# Schematic.net
KiCad netlist of a schematic drawn in EAGLE
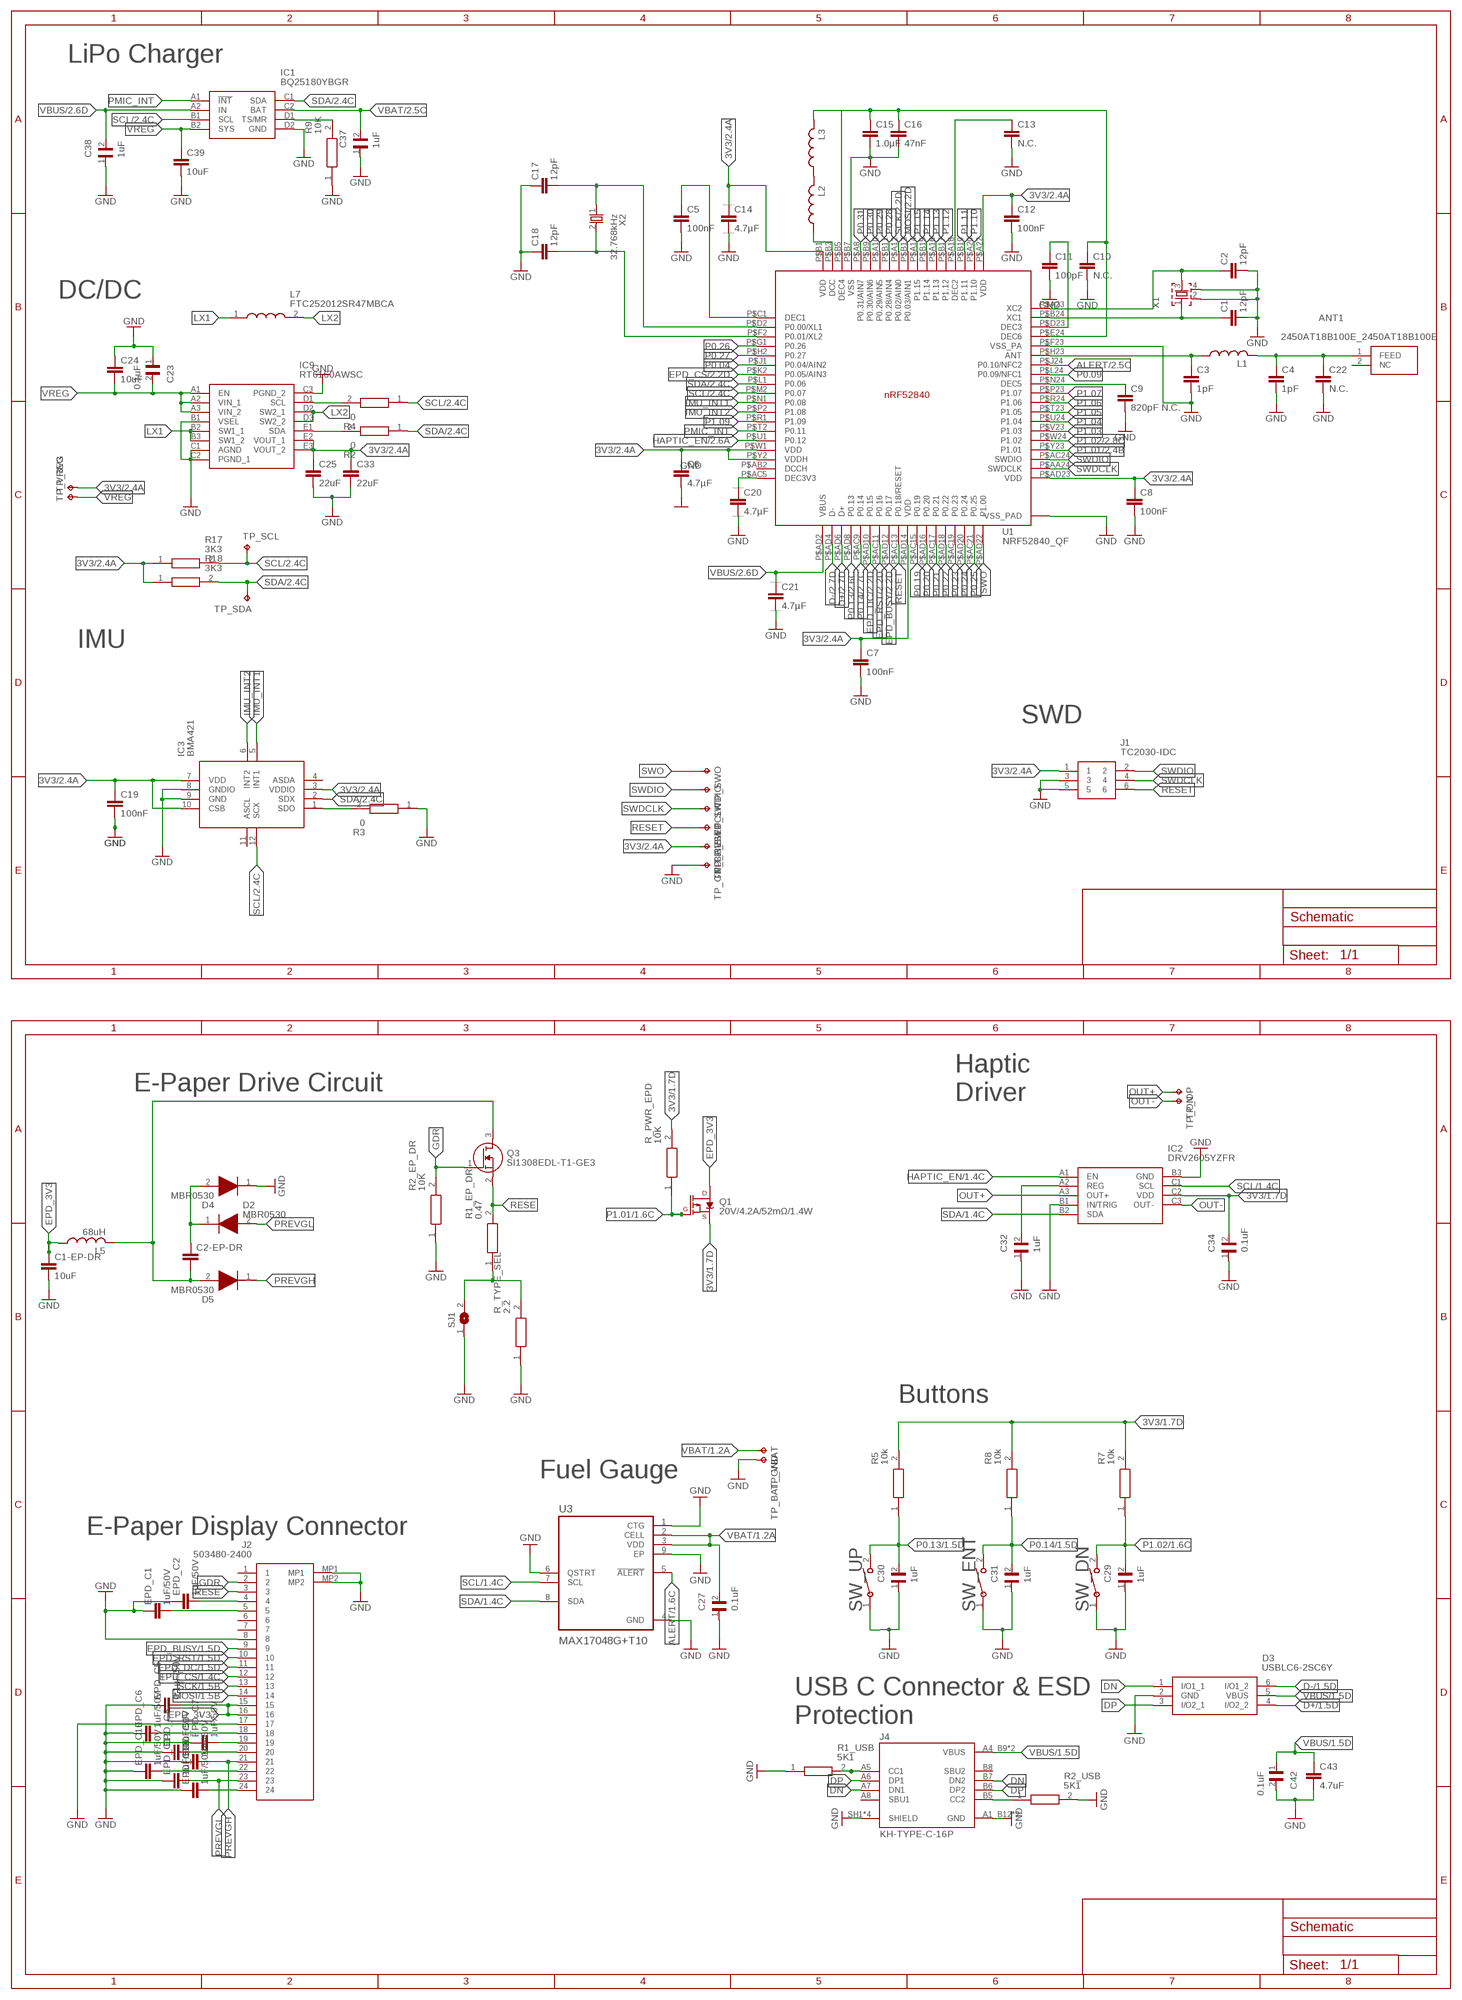
[diagram p0: schematic, sheet 1]

(export (version "E")
  (design (tool "Eeschema 10.0.6"))
  (components
    (comp (ref "ANT1")
      (value "2450AT18B100E_2450AT18B100E")
      (footprint "eagle-import:2450AT18B100E_ANTC3216X140N")
      (fields
        (field (name "ARROW_PART_NUMBER") "2450AT18B100E")
        (field (name "MOUSER_PART_NUMBER") "609-2450AT18B100E")
      )
      (libsource (lib "eagle-import") (part "2450AT18B100E_2450AT18B100E"))
    )
    (comp (ref "C1")
      (value "12pF")
      (footprint "eagle-import:NORDIC_NRF_3_RESC0201_L")
      (libsource (lib "eagle-import") (part "NORDIC_NRF_3_CAPACITOR_0201_L"))
    )
    (comp (ref "C1-EP-DR")
      (value "10uF")
      (footprint "eagle-import:NORDIC_NRF_3_RESC0201_L")
      (libsource (lib "eagle-import") (part "NORDIC_NRF_3_CAPACITOR_0201_L"))
    )
    (comp (ref "C2")
      (value "12pF")
      (footprint "eagle-import:NORDIC_NRF_3_RESC0201_L")
      (libsource (lib "eagle-import") (part "NORDIC_NRF_3_CAPACITOR_0201_L"))
    )
    (comp (ref "C2-EP-DR")
      (value "NORDIC_NRF_3_CAPACITOR_0201_L")
      (footprint "eagle-import:NORDIC_NRF_3_RESC0201_L")
      (libsource (lib "eagle-import") (part "NORDIC_NRF_3_CAPACITOR_0201_L"))
    )
    (comp (ref "C3")
      (value "1pF")
      (footprint "eagle-import:NORDIC_NRF_3_RESC0201_L")
      (libsource (lib "eagle-import") (part "NORDIC_NRF_3_CAPACITOR_0201_L"))
    )
    (comp (ref "C4")
      (value "1pF")
      (footprint "eagle-import:NORDIC_NRF_3_RESC0201_L")
      (libsource (lib "eagle-import") (part "NORDIC_NRF_3_CAPACITOR_0201_L"))
    )
    (comp (ref "C5")
      (value "100nF")
      (footprint "eagle-import:NORDIC_NRF_3_RESC0201_L")
      (libsource (lib "eagle-import") (part "NORDIC_NRF_3_CAPACITOR_0201_L"))
    )
    (comp (ref "C6")
      (value "4.7µF")
      (footprint "eagle-import:NORDIC_NRF_3_RESC0201_L")
      (libsource (lib "eagle-import") (part "NORDIC_NRF_3_CAPACITOR_0201_L"))
    )
    (comp (ref "C7")
      (value "100nF")
      (footprint "eagle-import:NORDIC_NRF_3_RESC0201_L")
      (libsource (lib "eagle-import") (part "NORDIC_NRF_3_CAPACITOR_0201_L"))
    )
    (comp (ref "C8")
      (value "100nF")
      (footprint "eagle-import:NORDIC_NRF_3_RESC0201_L")
      (libsource (lib "eagle-import") (part "NORDIC_NRF_3_CAPACITOR_0201_L"))
    )
    (comp (ref "C9")
      (value "820pF N.C.")
      (footprint "eagle-import:NORDIC_NRF_3_RESC0201_L")
      (libsource (lib "eagle-import") (part "NORDIC_NRF_3_CAPACITOR_0201_L"))
    )
    (comp (ref "C10")
      (value "N.C.")
      (footprint "eagle-import:NORDIC_NRF_3_RESC0201_L")
      (libsource (lib "eagle-import") (part "NORDIC_NRF_3_CAPACITOR_0201_L"))
    )
    (comp (ref "C11")
      (value "100pF")
      (footprint "eagle-import:NORDIC_NRF_3_RESC0201_L")
      (libsource (lib "eagle-import") (part "NORDIC_NRF_3_CAPACITOR_0201_L"))
    )
    (comp (ref "C12")
      (value "100nF")
      (footprint "eagle-import:NORDIC_NRF_3_RESC0201_L")
      (libsource (lib "eagle-import") (part "NORDIC_NRF_3_CAPACITOR_0201_L"))
    )
    (comp (ref "C13")
      (value "N.C.")
      (footprint "eagle-import:NORDIC_NRF_3_RESC0201_L")
      (libsource (lib "eagle-import") (part "NORDIC_NRF_3_CAPACITOR_0201_L"))
    )
    (comp (ref "C14")
      (value "4.7µF")
      (footprint "eagle-import:ESP32_C6_LIBRARY_1_ESP32_WROVER_EAGLE-LTSPICE_C0402")
      (libsource (lib "eagle-import") (part "ESP32_C6_LIBRARY_1_ESP32_WROVER_EAGLE-LTSPICE_CC0402"))
    )
    (comp (ref "C15")
      (value "1.0µF")
      (footprint "eagle-import:NORDIC_NRF_3_RESC0201_L")
      (libsource (lib "eagle-import") (part "NORDIC_NRF_3_CAPACITOR_0201_L"))
    )
    (comp (ref "C16")
      (value "47nF")
      (footprint "eagle-import:NORDIC_NRF_3_RESC0201_L")
      (libsource (lib "eagle-import") (part "NORDIC_NRF_3_CAPACITOR_0201_L"))
    )
    (comp (ref "C17")
      (value "12pF")
      (footprint "eagle-import:NORDIC_NRF_3_RESC0201_L")
      (libsource (lib "eagle-import") (part "NORDIC_NRF_3_CAPACITOR_0201_L"))
    )
    (comp (ref "C18")
      (value "12pF")
      (footprint "eagle-import:NORDIC_NRF_3_RESC0201_L")
      (libsource (lib "eagle-import") (part "NORDIC_NRF_3_CAPACITOR_0201_L"))
    )
    (comp (ref "C19")
      (value "100nF")
      (footprint "eagle-import:NORDIC_NRF_3_RESC0201_L")
      (libsource (lib "eagle-import") (part "NORDIC_NRF_3_CAPACITOR_0201_L"))
    )
    (comp (ref "C20")
      (value "4.7µF")
      (footprint "eagle-import:ESP32_C6_LIBRARY_1_ESP32_WROVER_EAGLE-LTSPICE_C0402")
      (libsource (lib "eagle-import") (part "ESP32_C6_LIBRARY_1_ESP32_WROVER_EAGLE-LTSPICE_CC0402"))
    )
    (comp (ref "C21")
      (value "4.7µF")
      (footprint "eagle-import:ESP32_C6_LIBRARY_1_ESP32_WROVER_EAGLE-LTSPICE_C0402")
      (libsource (lib "eagle-import") (part "ESP32_C6_LIBRARY_1_ESP32_WROVER_EAGLE-LTSPICE_CC0402"))
    )
    (comp (ref "C22")
      (value "N.C.")
      (footprint "eagle-import:NORDIC_NRF_3_RESC0201_L")
      (libsource (lib "eagle-import") (part "NORDIC_NRF_3_CAPACITOR_0201_L"))
    )
    (comp (ref "C23")
      (value "0.1uF")
      (footprint "eagle-import:GRM011R60J152KE01L_2_CAPC0201X13N")
      (fields (field (name "MF") "Murata") (field (name "MP") "GRM011R60J152KE01L"))
      (libsource (lib "eagle-import") (part "GRM011R60J152KE01L_2_GRM011R60J152KE01L"))
    )
    (comp (ref "C24")
      (value "10uF")
      (footprint "eagle-import:NORDIC_NRF_3_RESC0201_L")
      (libsource (lib "eagle-import") (part "InkTime_v5_vf.zRXQ1UkXTZ2guy9XbI6Eng_NORDIC_NRF_3_CAPACITOR_0201_L"))
    )
    (comp (ref "C25")
      (value "22uF")
      (footprint "eagle-import:NORDIC_NRF_3_RESC0201_L")
      (libsource (lib "eagle-import") (part "InkTime_v5_vf.zRXQ1UkXTZ2guy9XbI6Eng_NORDIC_NRF_3_CAPACITOR_0201_L"))
    )
    (comp (ref "C27")
      (value "0.1uF")
      (footprint "eagle-import:GRM011R60J152KE01L_1_0201")
      (libsource (lib "eagle-import") (part "GRM011R60J152KE01L_1_GRM011R60J152KE01L"))
    )
    (comp (ref "C29")
      (value "1uF")
      (footprint "eagle-import:GRM011R60J152KE01L_1_0201")
      (libsource (lib "eagle-import") (part "GRM011R60J152KE01L_1_GRM011R60J152KE01L"))
    )
    (comp (ref "C30")
      (value "1uF")
      (footprint "eagle-import:GRM011R60J152KE01L_1_0201")
      (libsource (lib "eagle-import") (part "GRM011R60J152KE01L_1_GRM011R60J152KE01L"))
    )
    (comp (ref "C31")
      (value "1uF")
      (footprint "eagle-import:GRM011R60J152KE01L_1_0201")
      (libsource (lib "eagle-import") (part "GRM011R60J152KE01L_1_GRM011R60J152KE01L"))
    )
    (comp (ref "C32")
      (value "1uF")
      (footprint "eagle-import:GRM011R60J152KE01L_2_CAPC0201X13N")
      (fields (field (name "MF") "Murata") (field (name "MP") "GRM011R60J152KE01L"))
      (libsource (lib "eagle-import") (part "GRM011R60J152KE01L_2_GRM011R60J152KE01L"))
    )
    (comp (ref "C33")
      (value "22uF")
      (footprint "eagle-import:NORDIC_NRF_3_RESC0201_L")
      (libsource (lib "eagle-import") (part "InkTime_v5_vf.zRXQ1UkXTZ2guy9XbI6Eng_NORDIC_NRF_3_CAPACITOR_0201_L"))
    )
    (comp (ref "C34")
      (value "0.1uF")
      (footprint "eagle-import:GRM011R60J152KE01L_2_CAPC0201X13N")
      (fields (field (name "MF") "Murata") (field (name "MP") "GRM011R60J152KE01L"))
      (libsource (lib "eagle-import") (part "GRM011R60J152KE01L_2_GRM011R60J152KE01L"))
    )
    (comp (ref "C37")
      (value "1uF")
      (footprint "eagle-import:GRM011R60J152KE01L_2_CAPC0201X13N")
      (fields (field (name "MF") "Murata") (field (name "MP") "GRM011R60J152KE01L"))
      (libsource (lib "eagle-import") (part "GRM011R60J152KE01L_2_GRM011R60J152KE01L"))
    )
    (comp (ref "C38")
      (value "1uF")
      (footprint "eagle-import:GRM011R60J152KE01L_2_CAPC0201X13N")
      (fields (field (name "MF") "Murata") (field (name "MP") "GRM011R60J152KE01L"))
      (libsource (lib "eagle-import") (part "GRM011R60J152KE01L_2_GRM011R60J152KE01L"))
    )
    (comp (ref "C39")
      (value "10uF")
      (footprint "eagle-import:NORDIC_NRF_3_RESC0201_L")
      (libsource (lib "eagle-import") (part "InkTime_v5_vf.zRXQ1UkXTZ2guy9XbI6Eng_NORDIC_NRF_3_CAPACITOR_0201_L"))
    )
    (comp (ref "C42")
      (value "0.1uF")
      (footprint "eagle-import:GRM011R60J152KE01L_1_0201")
      (libsource (lib "eagle-import") (part "GRM011R60J152KE01L_1_GRM011R60J152KE01L"))
    )
    (comp (ref "C43")
      (value "4.7uF")
      (footprint "eagle-import:NORDIC_NRF_3_RESC0201_L")
      (libsource (lib "eagle-import") (part "InkTime_v5_vf.zRXQ1UkXTZ2guy9XbI6Eng_NORDIC_NRF_3_CAPACITOR_0201_L"))
    )
    (comp (ref "D2")
      (value "MBR0530")
      (footprint "eagle-import:ESP32_C6_LIBRARY_5_SOD3716X135N")
      (fields (field (name "MF") "ON Semiconductor"))
      (libsource (lib "eagle-import") (part "ESP32_C6_LIBRARY_5_MBR0530"))
    )
    (comp (ref "D3")
      (value "USBLC6-2SC6Y")
      (footprint "eagle-import:ESP32_C6_LIBRARY_3_SOT95P280X145-6N")
      (fields (field (name "MF") "STMicroelectronics"))
      (libsource (lib "eagle-import") (part "ESP32_C6_LIBRARY_3_USBLC6-2SC6Y"))
    )
    (comp (ref "D4")
      (value "MBR0530")
      (footprint "eagle-import:ESP32_C6_LIBRARY_5_SOD3716X135N")
      (fields (field (name "MF") "ON Semiconductor"))
      (libsource (lib "eagle-import") (part "ESP32_C6_LIBRARY_5_MBR0530"))
    )
    (comp (ref "D5")
      (value "MBR0530")
      (footprint "eagle-import:ESP32_C6_LIBRARY_5_SOD3716X135N")
      (fields (field (name "MF") "ON Semiconductor"))
      (libsource (lib "eagle-import") (part "ESP32_C6_LIBRARY_5_MBR0530"))
    )
    (comp (ref "EPD_C1")
      (value "1uF/50V")
      (footprint "eagle-import:PERFECT_0402_0402")
      (libsource (lib "eagle-import") (part "PERFECT_0402_CAP_0402"))
    )
    (comp (ref "EPD_C2")
      (value "1uF/50V")
      (footprint "eagle-import:PERFECT_0402_0402")
      (libsource (lib "eagle-import") (part "PERFECT_0402_CAP_0402"))
    )
    (comp (ref "EPD_C5")
      (value "0.1uF/50V")
      (footprint "eagle-import:PERFECT_0402_0402")
      (libsource (lib "eagle-import") (part "PERFECT_0402_CAP_0402"))
    )
    (comp (ref "EPD_C6")
      (value "1uF/50V")
      (footprint "eagle-import:PERFECT_0402_0402")
      (libsource (lib "eagle-import") (part "PERFECT_0402_CAP_0402"))
    )
    (comp (ref "EPD_C7")
      (value "1uF/50V")
      (footprint "eagle-import:PERFECT_0402_0402")
      (libsource (lib "eagle-import") (part "PERFECT_0402_CAP_0402"))
    )
    (comp (ref "EPD_C8")
      (value "1uF/50V")
      (footprint "eagle-import:PERFECT_0402_0402")
      (libsource (lib "eagle-import") (part "PERFECT_0402_CAP_0402"))
    )
    (comp (ref "EPD_C9")
      (value "1uF/50V")
      (footprint "eagle-import:PERFECT_0402_0402")
      (libsource (lib "eagle-import") (part "PERFECT_0402_CAP_0402"))
    )
    (comp (ref "EPD_C10")
      (value "1uF/50V")
      (footprint "eagle-import:PERFECT_0402_0402")
      (libsource (lib "eagle-import") (part "PERFECT_0402_CAP_0402"))
    )
    (comp (ref "EPD_C11")
      (value "1uF/50V")
      (footprint "eagle-import:PERFECT_0402_0402")
      (libsource (lib "eagle-import") (part "PERFECT_0402_CAP_0402"))
    )
    (comp (ref "EPD_C12")
      (value "1uF/50V")
      (footprint "eagle-import:PERFECT_0402_0402")
      (libsource (lib "eagle-import") (part "PERFECT_0402_CAP_0402"))
    )
    (comp (ref "IC1")
      (value "BQ25180YBGR")
      (footprint "eagle-import:BQ25180YBGR_BGA8C40P2X4_100X155X50")
      (fields (field (name "MOUSER_PART_NUMBER") "595-BQ25180YBGR"))
      (libsource (lib "eagle-import") (part "BQ25180YBGR_BQ25180YBGR"))
    )
    (comp (ref "IC2")
      (value "DRV2605YZFR")
      (footprint "eagle-import:DRV2605YZFR_BGA9C50P3X3_144X144X62")
      (libsource (lib "eagle-import") (part "DRV2605YZFR_DRV2605YZFR"))
    )
    (comp (ref "IC3")
      (value "BMA421")
      (footprint "eagle-import:BMA423_BMA423")
      (fields (field (name "ARROW_PART_NUMBER") "BMA423") (field (name "MOUSER_PART_NUMBER") "262-BMA423"))
      (libsource (lib "eagle-import") (part "BMA423_BMA423"))
    )
    (comp (ref "IC9")
      (value "RT6160AWSC")
      (footprint "eagle-import:RT6160AWSC_BGA15C40P3X5_140X230X60")
      (fields (field (name "MOUSER_PART_NUMBER") "835-RT6160AWSC"))
      (libsource (lib "eagle-import") (part "RT6160AWSC_RT6160AWSC"))
    )
    (comp (ref "J1")
      (value "TC2030-IDC")
      (footprint "eagle-import:TC2030-IDC_TC2030IDC")
      (libsource (lib "eagle-import") (part "TC2030-IDC_TC2030-IDC"))
    )
    (comp (ref "J2")
      (value "503480-2400")
      (footprint "eagle-import:503480-2400_5034802400")
      (fields (field (name "MOUSER_PART_NUMBER") "538-503480-2400"))
      (libsource (lib "eagle-import") (part "503480-2400_503480-2400"))
    )
    (comp (ref "J4")
      (value "KH-TYPE-C-16P")
      (footprint "eagle-import:KH-TYPE-C-16P_KINGHELM_KH-TYPE-C-16P")
      (fields (field (name "MF") "kinghelm"))
      (libsource (lib "eagle-import") (part "KH-TYPE-C-16P_KH-TYPE-C-16P"))
    )
    (comp (ref "L1")
      (value "NORDIC_NRF_2_INDUCTOR_0402_L")
      (footprint "eagle-import:NORDIC_NRF_2_RESC0402_L")
      (libsource (lib "eagle-import") (part "NORDIC_NRF_2_INDUCTOR_0402_L"))
    )
    (comp (ref "L2")
      (value "NORDIC_NRF_2_INDUCTOR_0402_L")
      (footprint "eagle-import:NORDIC_NRF_2_RESC0402_L")
      (libsource (lib "eagle-import") (part "NORDIC_NRF_2_INDUCTOR_0402_L"))
    )
    (comp (ref "L3")
      (value "NORDIC_NRF_2_INDUCTOR_0402_L")
      (footprint "eagle-import:NORDIC_NRF_2_RESC0402_L")
      (libsource (lib "eagle-import") (part "NORDIC_NRF_2_INDUCTOR_0402_L"))
    )
    (comp (ref "L5")
      (value "68uH")
      (footprint "eagle-import:NORDIC_NRF_2_RESC0402_L")
      (libsource (lib "eagle-import") (part "NORDIC_NRF_2_INDUCTOR_0402_L"))
    )
    (comp (ref "L7")
      (value "FTC252012SR47MBCA")
      (footprint "eagle-import:MLP2016SR47MT0S1_INDC2016X100N")
      (libsource (lib "eagle-import") (part "MLP2016SR47MT0S1_FTC252012SR47MBCA"))
    )
    (comp (ref "Q1")
      (value "20V/4.2A/52mΩ/1.4W")
      (footprint "eagle-import:ESP32_C6_LIBRARY_4_ESP32_C6_LIBRARY_4_ESP32_C6_LIBRARY_4_ESP32_C6_LIBRARY_4_ESP32_WROVER_SPARKFUN-DISCRETESEMI_SOT23-3")
      (libsource (lib "eagle-import") (part "ESP32_C6_LIBRARY_4_ESP32_WROVER_SPARKFUN-DISCRETESEMI_MOSFET_PCH-DMG2305UX-7"))
    )
    (comp (ref "Q3")
      (value "SI1308EDL-T1-GE3")
      (footprint "eagle-import:ESP32_C6_LIBRARY_6_SOT65P210X110-3N")
      (fields (field (name "MF") "Vishay Siliconix"))
      (libsource (lib "eagle-import") (part "ESP32_C6_LIBRARY_6_SI1308EDL-T1-GE3"))
    )
    (comp (ref "R1_EP_DR")
      (value "0.47")
      (footprint "eagle-import:ERA-1AEB3401C_0201")
      (libsource (lib "eagle-import") (part "ERA-1AEB3401C_CPF0201D7K68C1"))
    )
    (comp (ref "R1_USB")
      (value "5K1")
      (footprint "eagle-import:CPF0201D7K68C1_0201")
      (libsource (lib "eagle-import") (part "InkTime_v5_vf.zRXQ1UkXTZ2guy9XbI6Eng_CPF0201D7K68C1_CPF0201D7K68C1"))
    )
    (comp (ref "R2")
      (value "0")
      (footprint "eagle-import:ERA-1AEB3401C_0201")
      (libsource (lib "eagle-import") (part "ERA-1AEB3401C_CPF0201D7K68C1"))
    )
    (comp (ref "R2_EP_DR")
      (value "10K")
      (footprint "eagle-import:ERA-1AEB3401C_0201")
      (libsource (lib "eagle-import") (part "ERA-1AEB3401C_CPF0201D7K68C1"))
    )
    (comp (ref "R2_USB")
      (value "5K1")
      (footprint "eagle-import:CPF0201D7K68C1_0201")
      (libsource (lib "eagle-import") (part "InkTime_v5_vf.zRXQ1UkXTZ2guy9XbI6Eng_CPF0201D7K68C1_CPF0201D7K68C1"))
    )
    (comp (ref "R3")
      (value "0")
      (footprint "eagle-import:CPF0201D7K68C1_0201")
      (libsource (lib "eagle-import") (part "CPF0201D7K68C1_CPF0201D7K68C1"))
    )
    (comp (ref "R4")
      (value "0")
      (footprint "eagle-import:ERA-1AEB3401C_0201")
      (libsource (lib "eagle-import") (part "ERA-1AEB3401C_CPF0201D7K68C1"))
    )
    (comp (ref "R5")
      (value "10k")
      (footprint "eagle-import:CPF0201D7K68C1_0201")
      (libsource (lib "eagle-import") (part "InkTime_v5_vf.zRXQ1UkXTZ2guy9XbI6Eng_CPF0201D7K68C1_CPF0201D7K68C1"))
    )
    (comp (ref "R7")
      (value "10k")
      (footprint "eagle-import:CPF0201D7K68C1_0201")
      (libsource (lib "eagle-import") (part "InkTime_v5_vf.zRXQ1UkXTZ2guy9XbI6Eng_CPF0201D7K68C1_CPF0201D7K68C1"))
    )
    (comp (ref "R8")
      (value "10k")
      (footprint "eagle-import:CPF0201D7K68C1_0201")
      (libsource (lib "eagle-import") (part "InkTime_v5_vf.zRXQ1UkXTZ2guy9XbI6Eng_CPF0201D7K68C1_CPF0201D7K68C1"))
    )
    (comp (ref "R9")
      (value "10K")
      (footprint "eagle-import:ERA-1AEB3401C_0201")
      (libsource (lib "eagle-import") (part "ERA-1AEB3401C_CPF0201D7K68C1"))
    )
    (comp (ref "R17")
      (value "3K3")
      (footprint "eagle-import:ERA-1AEB3401C_0201")
      (libsource (lib "eagle-import") (part "ERA-1AEB3401C_CPF0201D7K68C1"))
    )
    (comp (ref "R18")
      (value "3K3")
      (footprint "eagle-import:ERA-1AEB3401C_0201")
      (libsource (lib "eagle-import") (part "ERA-1AEB3401C_CPF0201D7K68C1"))
    )
    (comp (ref "R_PWR_EPD")
      (value "10K")
      (footprint "eagle-import:ERA-1AEB3401C_0201")
      (libsource (lib "eagle-import") (part "ERA-1AEB3401C_CPF0201D7K68C1"))
    )
    (comp (ref "R_TYPE_SEL")
      (value "2.2")
      (footprint "eagle-import:ERA-1AEB3401C_0201")
      (libsource (lib "eagle-import") (part "ERA-1AEB3401C_CPF0201D7K68C1"))
    )
    (comp (ref "SJ1")
      (value "ESP32_C6_LIBRARY_7_JUMPER_SJ")
      (footprint "eagle-import:ESP32_C6_LIBRARY_7_JUMPER_SJ")
      (libsource (lib "eagle-import") (part "ESP32_C6_LIBRARY_7_JUMPER_SJ"))
    )
    (comp (ref "SW_DN")
      (value "2025-10-22_07-23-44_LIBRARY_EVP-AKE31ASW_EVP-AKE31A_PAN")
      (footprint "eagle-import:2025-10-22_07-23-44_LIBRARY_SW_EVP-AKE31A_PAN")
      (fields
        (field (name "MANUFACTURER_PART_NUMBER") "EVP-AKE31A")
        (field (name "COPYRIGHT") "Copyright (C) 2025 Ultra Librarian. All rights reserved.")
      )
      (libsource (lib "eagle-import") (part "2025-10-22_07-23-44_LIBRARY_EVP-AKE31ASW_EVP-AKE31A_PAN"))
    )
    (comp (ref "SW_ENT")
      (value "2025-10-22_07-23-44_LIBRARY_EVP-AKE31ASW_EVP-AKE31A_PAN")
      (footprint "eagle-import:2025-10-22_07-23-44_LIBRARY_SW_EVP-AKE31A_PAN")
      (fields
        (field (name "MANUFACTURER_PART_NUMBER") "EVP-AKE31A")
        (field (name "COPYRIGHT") "Copyright (C) 2025 Ultra Librarian. All rights reserved.")
      )
      (libsource (lib "eagle-import") (part "2025-10-22_07-23-44_LIBRARY_EVP-AKE31ASW_EVP-AKE31A_PAN"))
    )
    (comp (ref "SW_UP")
      (value "2025-10-22_07-23-44_LIBRARY_EVP-AKE31ASW_EVP-AKE31A_PAN")
      (footprint "eagle-import:2025-10-22_07-23-44_LIBRARY_SW_EVP-AKE31A_PAN")
      (fields
        (field (name "MANUFACTURER_PART_NUMBER") "EVP-AKE31A")
        (field (name "COPYRIGHT") "Copyright (C) 2025 Ultra Librarian. All rights reserved.")
      )
      (libsource (lib "eagle-import") (part "2025-10-22_07-23-44_LIBRARY_EVP-AKE31ASW_EVP-AKE31A_PAN"))
    )
    (comp (ref "TP_3.3V")
      (value "HECTOR_WATCH_1_TPTP20R")
      (footprint "eagle-import:HECTOR_WATCH_1_TP20R")
      (libsource (lib "eagle-import") (part "HECTOR_WATCH_1_TPTP20R"))
    )
    (comp (ref "TP_3V3")
      (value "HECTOR_WATCH_1_TPTP20R")
      (footprint "eagle-import:HECTOR_WATCH_1_TP20R")
      (libsource (lib "eagle-import") (part "InkTime_v5_vf.zRXQ1UkXTZ2guy9XbI6Eng_HECTOR_WATCH_1_TPTP20R"))
    )
    (comp (ref "TP_BAT_GND")
      (value "HECTOR_WATCH_1_TPTP20R")
      (footprint "eagle-import:HECTOR_WATCH_1_TP20R")
      (libsource (lib "eagle-import") (part "InkTime_v5_vf.zRXQ1UkXTZ2guy9XbI6Eng_HECTOR_WATCH_1_TPTP20R"))
    )
    (comp (ref "TP_GND")
      (value "HECTOR_WATCH_1_TPTP20R")
      (footprint "eagle-import:HECTOR_WATCH_1_TP20R")
      (libsource (lib "eagle-import") (part "HECTOR_WATCH_1_TPTP20R"))
    )
    (comp (ref "TP_ON")
      (value "HECTOR_WATCH_1_TPTP20R")
      (footprint "eagle-import:HECTOR_WATCH_1_TP20R")
      (libsource (lib "eagle-import") (part "HECTOR_WATCH_1_TPTP20R"))
    )
    (comp (ref "TP_OP")
      (value "HECTOR_WATCH_1_TPTP20R")
      (footprint "eagle-import:HECTOR_WATCH_1_TP20R")
      (libsource (lib "eagle-import") (part "HECTOR_WATCH_1_TPTP20R"))
    )
    (comp (ref "TP_RESET")
      (value "HECTOR_WATCH_1_TPTP20R")
      (footprint "eagle-import:HECTOR_WATCH_1_TP20R")
      (libsource (lib "eagle-import") (part "HECTOR_WATCH_1_TPTP20R"))
    )
    (comp (ref "TP_SCL")
      (value "HECTOR_WATCH_1_TPTP20R")
      (footprint "eagle-import:HECTOR_WATCH_1_TP20R")
      (libsource (lib "eagle-import") (part "HECTOR_WATCH_1_TPTP20R"))
    )
    (comp (ref "TP_SDA")
      (value "HECTOR_WATCH_1_TPTP20R")
      (footprint "eagle-import:HECTOR_WATCH_1_TP20R")
      (libsource (lib "eagle-import") (part "HECTOR_WATCH_1_TPTP20R"))
    )
    (comp (ref "TP_SWDCLK")
      (value "HECTOR_WATCH_1_TPTP20R")
      (footprint "eagle-import:HECTOR_WATCH_1_TP20R")
      (libsource (lib "eagle-import") (part "HECTOR_WATCH_1_TPTP20R"))
    )
    (comp (ref "TP_SWDIO")
      (value "HECTOR_WATCH_1_TPTP20R")
      (footprint "eagle-import:HECTOR_WATCH_1_TP20R")
      (libsource (lib "eagle-import") (part "HECTOR_WATCH_1_TPTP20R"))
    )
    (comp (ref "TP_SWO")
      (value "HECTOR_WATCH_1_TPTP20R")
      (footprint "eagle-import:HECTOR_WATCH_1_TP20R")
      (libsource (lib "eagle-import") (part "HECTOR_WATCH_1_TPTP20R"))
    )
    (comp (ref "TP_VBAT")
      (value "HECTOR_WATCH_1_TPTP20R")
      (footprint "eagle-import:HECTOR_WATCH_1_TP20R")
      (libsource (lib "eagle-import") (part "InkTime_v5_vf.zRXQ1UkXTZ2guy9XbI6Eng_HECTOR_WATCH_1_TPTP20R"))
    )
    (comp (ref "TP_VREG")
      (value "HECTOR_WATCH_1_TPTP20R")
      (footprint "eagle-import:HECTOR_WATCH_1_TP20R")
      (libsource (lib "eagle-import") (part "InkTime_v5_vf.zRXQ1UkXTZ2guy9XbI6Eng_HECTOR_WATCH_1_TPTP20R"))
    )
    (comp (ref "U1")
      (value "NRF52840_QF")
      (footprint "eagle-import:NORDIC_NRF_4_AQFN50P700X700X85_HS-74N")
      (libsource (lib "eagle-import") (part "NORDIC_NRF_4_NRF52840_QF"))
    )
    (comp (ref "U3")
      (value "MAX17048G+T10")
      (footprint "eagle-import:ESP32_C6_LIBRARY_SON50P200X200X80-9N")
      (fields (field (name "MF") "Analog Devices"))
      (libsource (lib "eagle-import") (part "ESP32_C6_LIBRARY_MAX17048G+T10"))
    )
    (comp (ref "X1")
      (value "NORDIC_NRF_XTAL_32MHZ")
      (footprint "eagle-import:NORDIC_NRF_BT-XTAL_2016_N")
      (libsource (lib "eagle-import") (part "NORDIC_NRF_XTAL_32MHZ"))
    )
    (comp (ref "X2")
      (value "32.768kHz")
      (footprint "eagle-import:NORDIC_NRF_1_XTAL_3215_N")
      (libsource (lib "eagle-import") (part "NORDIC_NRF_1_XTAL_32KHZ"))
    )
  )
  (nets
    (net (code "1") (name "3V3{slash}1.7D") (class "Default")
      (node (ref "C34") (pin "2") (pinfunction "2_2") (pintype "passive"))
      (node (ref "IC2") (pin "C2") (pinfunction "VDD_C2") (pintype "bidirectional"))
      (node (ref "Q1") (pin "2") (pinfunction "S_2") (pintype "bidirectional"))
      (node (ref "R5") (pin "2") (pinfunction "2_2") (pintype "bidirectional"))
      (node (ref "R7") (pin "2") (pinfunction "2_2") (pintype "bidirectional"))
      (node (ref "R8") (pin "2") (pinfunction "2_2") (pintype "bidirectional"))
      (node (ref "R_PWR_EPD") (pin "2") (pinfunction "2_2") (pintype "bidirectional"))
    )
    (net (code "2") (name "3V3{slash}2.4A") (class "Default")
      (node (ref "C12") (pin "1") (pinfunction "1_1") (pintype "passive"))
      (node (ref "C14") (pin "1") (pinfunction "1_1") (pintype "passive"))
      (node (ref "C19") (pin "1") (pinfunction "1_1") (pintype "passive"))
      (node (ref "C25") (pin "1") (pinfunction "1_1") (pintype "passive"))
      (node (ref "C33") (pin "1") (pinfunction "1_1") (pintype "passive"))
      (node (ref "C6") (pin "1") (pinfunction "1_1") (pintype "passive"))
      (node (ref "C7") (pin "1") (pinfunction "1_1") (pintype "passive"))
      (node (ref "C8") (pin "1") (pinfunction "1_1") (pintype "passive"))
      (node (ref "IC3") (pin "10") (pinfunction "CSB_10") (pintype "bidirectional"))
      (node (ref "IC3") (pin "3") (pinfunction "VDDIO_3") (pintype "bidirectional"))
      (node (ref "IC3") (pin "7") (pinfunction "VDD_7") (pintype "bidirectional"))
      (node (ref "IC9") (pin "E2") (pinfunction "VOUT_1_E2") (pintype "bidirectional"))
      (node (ref "IC9") (pin "E3") (pinfunction "VOUT_2_E3") (pintype "bidirectional"))
      (node (ref "J1") (pin "1") (pinfunction "1_1") (pintype "bidirectional"))
      (node (ref "R17") (pin "1") (pinfunction "1_1") (pintype "bidirectional"))
      (node (ref "R18") (pin "1") (pinfunction "1_1") (pintype "bidirectional"))
      (node (ref "TP_3.3V") (pin "TP") (pinfunction "TP_TP") (pintype "input"))
      (node (ref "TP_3V3") (pin "TP") (pinfunction "TP_TP") (pintype "input"))
      (node (ref "U1") (pin "P$A22") (pinfunction "VDD_P$A22") (pintype "power_in"))
      (node (ref "U1") (pin "P$AD14") (pinfunction "VDD_P$AD14") (pintype "power_in"))
      (node (ref "U1") (pin "P$AD23") (pinfunction "VDD_P$AD23") (pintype "power_in"))
      (node (ref "U1") (pin "P$B1") (pinfunction "VDD_P$B1") (pintype "power_in"))
      (node (ref "U1") (pin "P$W1") (pinfunction "VDD_P$W1") (pintype "power_in"))
      (node (ref "U1") (pin "P$Y2") (pinfunction "VDDH_P$Y2") (pintype "power_in"))
    )
    (net (code "3") (name "ALERT{slash}1.6C") (class "Default")
      (node (ref "U3") (pin "5") (pinfunction "~{ALERT}_5") (pintype "output"))
    )
    (net (code "4") (name "ALERT{slash}2.5C") (class "Default")
      (node (ref "U1") (pin "P$J24") (pinfunction "P0.10/NFC2_P$J24") (pintype "bidirectional"))
    )
    (net (code "5") (name "D+{slash}1.5D") (class "Default")
      (node (ref "D3") (pin "4") (pinfunction "I/O2_2_4") (pintype "bidirectional"))
    )
    (net (code "6") (name "D+{slash}2.7D") (class "Default")
      (node (ref "U1") (pin "P$AD6") (pinfunction "D+_P$AD6") (pintype "bidirectional"))
    )
    (net (code "7") (name "D-{slash}1.5D") (class "Default")
      (node (ref "D3") (pin "6") (pinfunction "I/O1_2_6") (pintype "bidirectional"))
    )
    (net (code "8") (name "D-{slash}2.7D") (class "Default")
      (node (ref "U1") (pin "P$AD4") (pinfunction "D-_P$AD4") (pintype "bidirectional"))
    )
    (net (code "9") (name "DN") (class "Default")
      (node (ref "D3") (pin "1") (pinfunction "I/O1_1_1") (pintype "bidirectional"))
      (node (ref "J4") (pin "A7") (pinfunction "DN1_A7") (pintype "bidirectional"))
      (node (ref "J4") (pin "B7") (pinfunction "DN2_B7") (pintype "bidirectional"))
    )
    (net (code "10") (name "DP") (class "Default")
      (node (ref "D3") (pin "3") (pinfunction "I/O2_1_3") (pintype "bidirectional"))
      (node (ref "J4") (pin "A6") (pinfunction "DP1_A6") (pintype "bidirectional"))
      (node (ref "J4") (pin "B6") (pinfunction "DP2_B6") (pintype "bidirectional"))
    )
    (net (code "11") (name "EPD_3V3") (class "Default")
      (node (ref "C1-EP-DR") (pin "1") (pinfunction "1_1") (pintype "passive"))
      (node (ref "EPD_C5") (pin "2") (pinfunction "2_2") (pintype "passive"))
      (node (ref "J2") (pin "15") (pinfunction "15_15") (pintype "bidirectional"))
      (node (ref "J2") (pin "16") (pinfunction "16_16") (pintype "bidirectional"))
      (node (ref "L5") (pin "1") (pinfunction "1_1") (pintype "passive"))
      (node (ref "Q1") (pin "3") (pinfunction "D_3") (pintype "bidirectional"))
    )
    (net (code "12") (name "EPD_BUSY{slash}1.5D") (class "Default")
      (node (ref "J2") (pin "9") (pinfunction "9_9") (pintype "bidirectional"))
    )
    (net (code "13") (name "EPD_BUSY{slash}2.2D") (class "Default")
      (node (ref "U1") (pin "P$AD12") (pinfunction "P0.17_P$AD12") (pintype "bidirectional"))
    )
    (net (code "14") (name "EPD_CS{slash}1.4C") (class "Default")
      (node (ref "J2") (pin "12") (pinfunction "12_12") (pintype "bidirectional"))
    )
    (net (code "15") (name "EPD_CS{slash}2.2D") (class "Default")
      (node (ref "U1") (pin "P$K2") (pinfunction "P0.05/AIN3_P$K2") (pintype "bidirectional"))
    )
    (net (code "16") (name "EPD_DC{slash}1.5D") (class "Default")
      (node (ref "J2") (pin "11") (pinfunction "11_11") (pintype "bidirectional"))
    )
    (net (code "17") (name "EPD_DC{slash}2.2D") (class "Default")
      (node (ref "U1") (pin "P$AD10") (pinfunction "P0.15_P$AD10") (pintype "bidirectional"))
    )
    (net (code "18") (name "EPD_RST{slash}1.5D") (class "Default")
      (node (ref "J2") (pin "10") (pinfunction "10_10") (pintype "bidirectional"))
    )
    (net (code "19") (name "EPD_RST{slash}2.2D") (class "Default")
      (node (ref "U1") (pin "P$AC11") (pinfunction "P0.16_P$AC11") (pintype "bidirectional"))
    )
    (net (code "20") (name "GDR") (class "Default")
      (node (ref "J2") (pin "2") (pinfunction "2_2") (pintype "bidirectional"))
      (node (ref "Q3") (pin "1") (pinfunction "G_1") (pintype "bidirectional"))
      (node (ref "R2_EP_DR") (pin "2") (pinfunction "2_2") (pintype "bidirectional"))
    )
    (net (code "21") (name "GND") (class "Default")
      (node (ref "C1") (pin "2") (pinfunction "2_2") (pintype "passive"))
      (node (ref "C1-EP-DR") (pin "2") (pinfunction "2_2") (pintype "passive"))
      (node (ref "C10") (pin "2") (pinfunction "2_2") (pintype "passive"))
      (node (ref "C11") (pin "2") (pinfunction "2_2") (pintype "passive"))
      (node (ref "C12") (pin "2") (pinfunction "2_2") (pintype "passive"))
      (node (ref "C13") (pin "2") (pinfunction "2_2") (pintype "passive"))
      (node (ref "C14") (pin "2") (pinfunction "2_2") (pintype "passive"))
      (node (ref "C15") (pin "2") (pinfunction "2_2") (pintype "passive"))
      (node (ref "C16") (pin "2") (pinfunction "2_2") (pintype "passive"))
      (node (ref "C17") (pin "1") (pinfunction "1_1") (pintype "passive"))
      (node (ref "C18") (pin "1") (pinfunction "1_1") (pintype "passive"))
      (node (ref "C19") (pin "2") (pinfunction "2_2") (pintype "passive"))
      (node (ref "C2") (pin "2") (pinfunction "2_2") (pintype "passive"))
      (node (ref "C20") (pin "2") (pinfunction "2_2") (pintype "passive"))
      (node (ref "C21") (pin "2") (pinfunction "2_2") (pintype "passive"))
      (node (ref "C22") (pin "2") (pinfunction "2_2") (pintype "passive"))
      (node (ref "C23") (pin "1") (pinfunction "1_1") (pintype "passive"))
      (node (ref "C24") (pin "1") (pinfunction "1_1") (pintype "passive"))
      (node (ref "C25") (pin "2") (pinfunction "2_2") (pintype "passive"))
      (node (ref "C27") (pin "1") (pinfunction "1_1") (pintype "passive"))
      (node (ref "C29") (pin "1") (pinfunction "1_1") (pintype "passive"))
      (node (ref "C3") (pin "2") (pinfunction "2_2") (pintype "passive"))
      (node (ref "C30") (pin "1") (pinfunction "1_1") (pintype "passive"))
      (node (ref "C31") (pin "1") (pinfunction "1_1") (pintype "passive"))
      (node (ref "C32") (pin "1") (pinfunction "1_1") (pintype "passive"))
      (node (ref "C33") (pin "2") (pinfunction "2_2") (pintype "passive"))
      (node (ref "C34") (pin "1") (pinfunction "1_1") (pintype "passive"))
      (node (ref "C37") (pin "1") (pinfunction "1_1") (pintype "passive"))
      (node (ref "C38") (pin "1") (pinfunction "1_1") (pintype "passive"))
      (node (ref "C39") (pin "2") (pinfunction "2_2") (pintype "passive"))
      (node (ref "C4") (pin "2") (pinfunction "2_2") (pintype "passive"))
      (node (ref "C42") (pin "2") (pinfunction "2_2") (pintype "passive"))
      (node (ref "C43") (pin "2") (pinfunction "2_2") (pintype "passive"))
      (node (ref "C5") (pin "2") (pinfunction "2_2") (pintype "passive"))
      (node (ref "C6") (pin "2") (pinfunction "2_2") (pintype "passive"))
      (node (ref "C7") (pin "2") (pinfunction "2_2") (pintype "passive"))
      (node (ref "C8") (pin "2") (pinfunction "2_2") (pintype "passive"))
      (node (ref "C9") (pin "2") (pinfunction "2_2") (pintype "passive"))
      (node (ref "D3") (pin "2") (pinfunction "GND_2") (pintype "bidirectional"))
      (node (ref "D4") (pin "1") (pinfunction "K_1") (pintype "bidirectional"))
      (node (ref "EPD_C1") (pin "1") (pinfunction "1_1") (pintype "passive"))
      (node (ref "EPD_C10") (pin "1") (pinfunction "1_1") (pintype "passive"))
      (node (ref "EPD_C11") (pin "1") (pinfunction "1_1") (pintype "passive"))
      (node (ref "EPD_C12") (pin "1") (pinfunction "1_1") (pintype "passive"))
      (node (ref "EPD_C2") (pin "1") (pinfunction "1_1") (pintype "passive"))
      (node (ref "EPD_C5") (pin "1") (pinfunction "1_1") (pintype "passive"))
      (node (ref "EPD_C6") (pin "1") (pinfunction "1_1") (pintype "passive"))
      (node (ref "EPD_C7") (pin "1") (pinfunction "1_1") (pintype "passive"))
      (node (ref "EPD_C8") (pin "1") (pinfunction "1_1") (pintype "passive"))
      (node (ref "EPD_C9") (pin "1") (pinfunction "1_1") (pintype "passive"))
      (node (ref "IC1") (pin "D2") (pinfunction "GND_D2") (pintype "bidirectional"))
      (node (ref "IC2") (pin "B1") (pinfunction "IN/TRIG_B1") (pintype "bidirectional"))
      (node (ref "IC2") (pin "B3") (pinfunction "GND_B3") (pintype "bidirectional"))
      (node (ref "IC3") (pin "8") (pinfunction "GNDIO_8") (pintype "bidirectional"))
      (node (ref "IC3") (pin "9") (pinfunction "GND_9") (pintype "bidirectional"))
      (node (ref "IC9") (pin "B1") (pinfunction "VSEL_B1") (pintype "bidirectional"))
      (node (ref "IC9") (pin "C1") (pinfunction "AGND_C1") (pintype "bidirectional"))
      (node (ref "IC9") (pin "C2") (pinfunction "PGND_1_C2") (pintype "bidirectional"))
      (node (ref "IC9") (pin "C3") (pinfunction "PGND_2_C3") (pintype "bidirectional"))
      (node (ref "J1") (pin "3") (pinfunction "3_3") (pintype "bidirectional"))
      (node (ref "J1") (pin "5") (pinfunction "5_5") (pintype "bidirectional"))
      (node (ref "J2") (pin "17") (pinfunction "17_17") (pintype "bidirectional"))
      (node (ref "J2") (pin "8") (pinfunction "8_8") (pintype "bidirectional"))
      (node (ref "J2") (pin "MP1") (pinfunction "MP1_MP1") (pintype "bidirectional"))
      (node (ref "J2") (pin "MP2") (pinfunction "MP2_MP2") (pintype "bidirectional"))
      (node (ref "J4") (pin "A12_B1") (pinfunction "GND_A12_B1") (pintype "power_in"))
      (node (ref "J4") (pin "A1_B12") (pinfunction "GND_A1_B12") (pintype "power_in"))
      (node (ref "J4") (pin "SH1") (pinfunction "SHIELD_SH1") (pintype "passive"))
      (node (ref "J4") (pin "SH2") (pinfunction "SHIELD_SH2") (pintype "passive"))
      (node (ref "J4") (pin "SH3") (pinfunction "SHIELD_SH3") (pintype "passive"))
      (node (ref "J4") (pin "SH4") (pinfunction "SHIELD_SH4") (pintype "passive"))
      (node (ref "R1_USB") (pin "1") (pinfunction "1_1") (pintype "bidirectional"))
      (node (ref "R2_EP_DR") (pin "1") (pinfunction "1_1") (pintype "bidirectional"))
      (node (ref "R2_USB") (pin "2") (pinfunction "2_2") (pintype "bidirectional"))
      (node (ref "R3") (pin "1") (pinfunction "1_1") (pintype "bidirectional"))
      (node (ref "R9") (pin "1") (pinfunction "1_1") (pintype "bidirectional"))
      (node (ref "R_TYPE_SEL") (pin "1") (pinfunction "1_1") (pintype "bidirectional"))
      (node (ref "SJ1") (pin "1") (pinfunction "1_1") (pintype "passive"))
      (node (ref "SW_DN") (pin "1") (pinfunction "1_1") (pintype "passive"))
      (node (ref "SW_ENT") (pin "1") (pinfunction "1_1") (pintype "passive"))
      (node (ref "SW_UP") (pin "1") (pinfunction "1_1") (pintype "passive"))
      (node (ref "TP_BAT_GND") (pin "TP") (pinfunction "TP_TP") (pintype "input"))
      (node (ref "TP_GND") (pin "TP") (pinfunction "TP_TP") (pintype "input"))
      (node (ref "U1") (pin "P$74") (pinfunction "VSS_PAD_P$74") (pintype "bidirectional"))
      (node (ref "U1") (pin "P$75") (pinfunction "VSS_PAD_P$75") (pintype "bidirectional"))
      (node (ref "U1") (pin "P$76") (pinfunction "VSS_PAD_P$76") (pintype "bidirectional"))
      (node (ref "U1") (pin "P$77") (pinfunction "VSS_PAD_P$77") (pintype "bidirectional"))
      (node (ref "U1") (pin "P$78") (pinfunction "VSS_PAD_P$78") (pintype "bidirectional"))
      (node (ref "U1") (pin "P$79") (pinfunction "VSS_PAD_P$79") (pintype "bidirectional"))
      (node (ref "U1") (pin "P$80") (pinfunction "VSS_PAD_P$80") (pintype "bidirectional"))
      (node (ref "U1") (pin "P$81") (pinfunction "VSS_PAD_P$81") (pintype "bidirectional"))
      (node (ref "U1") (pin "P$82") (pinfunction "VSS_PAD_P$82") (pintype "bidirectional"))
      (node (ref "U1") (pin "P$83") (pinfunction "VSS_PAD_P$83") (pintype "bidirectional"))
      (node (ref "U1") (pin "P$84") (pinfunction "VSS_PAD_P$84") (pintype "bidirectional"))
      (node (ref "U1") (pin "P$85") (pinfunction "VSS_PAD_P$85") (pintype "bidirectional"))
      (node (ref "U1") (pin "P$86") (pinfunction "VSS_PAD_P$86") (pintype "bidirectional"))
      (node (ref "U1") (pin "P$87") (pinfunction "VSS_PAD_P$87") (pintype "bidirectional"))
      (node (ref "U1") (pin "P$88") (pinfunction "VSS_PAD_P$88") (pintype "bidirectional"))
      (node (ref "U1") (pin "P$89") (pinfunction "VSS_PAD_P$89") (pintype "bidirectional"))
      (node (ref "U1") (pin "P$90") (pinfunction "VSS_PAD_P$90") (pintype "bidirectional"))
      (node (ref "U1") (pin "P$B7") (pinfunction "VSS_P$B7") (pintype "power_in"))
      (node (ref "U1") (pin "P$F23") (pinfunction "VSS_PA_P$F23") (pintype "bidirectional"))
      (node (ref "U3") (pin "1") (pinfunction "CTG_1") (pintype "power_in"))
      (node (ref "U3") (pin "4") (pinfunction "GND_4") (pintype "power_in"))
      (node (ref "U3") (pin "6") (pinfunction "QSTRT_6") (pintype "input"))
      (node (ref "U3") (pin "9") (pinfunction "EP_9") (pintype "power_in"))
      (node (ref "X1") (pin "2") (pinfunction "2_2") (pintype "passive"))
      (node (ref "X1") (pin "4") (pinfunction "4_4") (pintype "passive"))
    )
    (net (code "22") (name "HAPTIC_EN{slash}1.4C") (class "Default")
      (node (ref "IC2") (pin "A1") (pinfunction "EN_A1") (pintype "bidirectional"))
    )
    (net (code "23") (name "HAPTIC_EN{slash}2.6A") (class "Default")
      (node (ref "U1") (pin "P$U1") (pinfunction "P0.12_P$U1") (pintype "bidirectional"))
    )
    (net (code "24") (name "IMU_INT1") (class "Default")
      (node (ref "IC3") (pin "5") (pinfunction "INT1_5") (pintype "bidirectional"))
      (node (ref "U1") (pin "P$N1") (pinfunction "P0.08_P$N1") (pintype "bidirectional"))
    )
    (net (code "25") (name "IMU_INT2") (class "Default")
      (node (ref "IC3") (pin "6") (pinfunction "INT2_6") (pintype "bidirectional"))
      (node (ref "U1") (pin "P$P2") (pinfunction "P1.08_P$P2") (pintype "bidirectional"))
    )
    (net (code "26") (name "LX1") (class "Default")
      (node (ref "IC9") (pin "B2") (pinfunction "SW1_1_B2") (pintype "bidirectional"))
      (node (ref "IC9") (pin "B3") (pinfunction "SW1_2_B3") (pintype "bidirectional"))
      (node (ref "L7") (pin "1") (pinfunction "1_1") (pintype "bidirectional"))
    )
    (net (code "27") (name "LX2") (class "Default")
      (node (ref "IC9") (pin "D2") (pinfunction "SW2_1_D2") (pintype "bidirectional"))
      (node (ref "IC9") (pin "D3") (pinfunction "SW2_2_D3") (pintype "bidirectional"))
      (node (ref "L7") (pin "2") (pinfunction "2_2") (pintype "bidirectional"))
    )
    (net (code "28") (name "MOSI{slash}1.5B") (class "Default")
      (node (ref "J2") (pin "14") (pinfunction "14_14") (pintype "bidirectional"))
    )
    (net (code "29") (name "MOSI{slash}2.2D") (class "Default")
      (node (ref "U1") (pin "P$B13") (pinfunction "P0.03/AIN1_P$B13") (pintype "bidirectional"))
    )
    (net (code "30") (name "Net-(ANT1-FEED)") (class "Default")
      (node (ref "ANT1") (pin "1") (pinfunction "FEED_1") (pintype "input"))
      (node (ref "C22") (pin "1") (pinfunction "1_1") (pintype "passive"))
      (node (ref "C4") (pin "1") (pinfunction "1_1") (pintype "passive"))
      (node (ref "L1") (pin "2") (pinfunction "2_2") (pintype "passive"))
    )
    (net (code "31") (name "Net-(D2-K)") (class "Default")
      (node (ref "C2-EP-DR") (pin "1") (pinfunction "1_1") (pintype "passive"))
      (node (ref "D2") (pin "1") (pinfunction "K_1") (pintype "bidirectional"))
      (node (ref "D4") (pin "2") (pinfunction "A_2") (pintype "bidirectional"))
    )
    (net (code "32") (name "Net-(D5-A)") (class "Default")
      (node (ref "C2-EP-DR") (pin "2") (pinfunction "2_2") (pintype "passive"))
      (node (ref "D5") (pin "2") (pinfunction "A_2") (pintype "bidirectional"))
      (node (ref "L5") (pin "2") (pinfunction "2_2") (pintype "passive"))
      (node (ref "Q3") (pin "3") (pinfunction "D_3") (pintype "bidirectional"))
    )
    (net (code "33") (name "Net-(EPD_C1-Pad2)") (class "Default")
      (node (ref "EPD_C1") (pin "2") (pinfunction "2_2") (pintype "passive"))
      (node (ref "J2") (pin "5") (pinfunction "5_5") (pintype "bidirectional"))
    )
    (net (code "34") (name "Net-(EPD_C2-Pad2)") (class "Default")
      (node (ref "EPD_C2") (pin "2") (pinfunction "2_2") (pintype "passive"))
      (node (ref "J2") (pin "4") (pinfunction "4_4") (pintype "bidirectional"))
    )
    (net (code "35") (name "Net-(EPD_C6-Pad2)") (class "Default")
      (node (ref "EPD_C6") (pin "2") (pinfunction "2_2") (pintype "passive"))
      (node (ref "J2") (pin "18") (pinfunction "18_18") (pintype "bidirectional"))
    )
    (net (code "36") (name "Net-(EPD_C7-Pad2)") (class "Default")
      (node (ref "EPD_C7") (pin "2") (pinfunction "2_2") (pintype "passive"))
      (node (ref "J2") (pin "19") (pinfunction "19_19") (pintype "bidirectional"))
    )
    (net (code "37") (name "Net-(EPD_C8-Pad2)") (class "Default")
      (node (ref "EPD_C8") (pin "2") (pinfunction "2_2") (pintype "passive"))
      (node (ref "J2") (pin "20") (pinfunction "20_20") (pintype "bidirectional"))
    )
    (net (code "38") (name "Net-(EPD_C10-Pad2)") (class "Default")
      (node (ref "EPD_C10") (pin "2") (pinfunction "2_2") (pintype "passive"))
      (node (ref "J2") (pin "22") (pinfunction "22_22") (pintype "bidirectional"))
    )
    (net (code "39") (name "Net-(EPD_C12-Pad2)") (class "Default")
      (node (ref "EPD_C12") (pin "2") (pinfunction "2_2") (pintype "passive"))
      (node (ref "J2") (pin "24") (pinfunction "24_24") (pintype "bidirectional"))
    )
    (net (code "40") (name "Net-(IC1-TS{slash}MR)") (class "Default")
      (node (ref "IC1") (pin "D1") (pinfunction "TS/MR_D1") (pintype "bidirectional"))
      (node (ref "R9") (pin "2") (pinfunction "2_2") (pintype "bidirectional"))
    )
    (net (code "41") (name "Net-(IC2-REG)") (class "Default")
      (node (ref "C32") (pin "2") (pinfunction "2_2") (pintype "passive"))
      (node (ref "IC2") (pin "A2") (pinfunction "REG_A2") (pintype "bidirectional"))
    )
    (net (code "42") (name "Net-(IC3-SDO)") (class "Default")
      (node (ref "IC3") (pin "1") (pinfunction "SDO_1") (pintype "bidirectional"))
      (node (ref "R3") (pin "2") (pinfunction "2_2") (pintype "bidirectional"))
    )
    (net (code "43") (name "Net-(IC9-SCL)") (class "Default")
      (node (ref "IC9") (pin "D1") (pinfunction "SCL_D1") (pintype "bidirectional"))
      (node (ref "R4") (pin "2") (pinfunction "2_2") (pintype "bidirectional"))
    )
    (net (code "44") (name "Net-(IC9-SDA)") (class "Default")
      (node (ref "IC9") (pin "E1") (pinfunction "SDA_E1") (pintype "bidirectional"))
      (node (ref "R2") (pin "2") (pinfunction "2_2") (pintype "bidirectional"))
    )
    (net (code "45") (name "Net-(J4-CC1)") (class "Default")
      (node (ref "J4") (pin "A5") (pinfunction "CC1_A5") (pintype "bidirectional"))
      (node (ref "R1_USB") (pin "2") (pinfunction "2_2") (pintype "bidirectional"))
    )
    (net (code "46") (name "Net-(J4-CC2)") (class "Default")
      (node (ref "J4") (pin "B5") (pinfunction "CC2_B5") (pintype "bidirectional"))
      (node (ref "R2_USB") (pin "1") (pinfunction "1_1") (pintype "bidirectional"))
    )
    (net (code "47") (name "Net-(L2-Pad2)") (class "Default")
      (node (ref "L2") (pin "2") (pinfunction "2_2") (pintype "passive"))
      (node (ref "L3") (pin "1") (pinfunction "1_1") (pintype "passive"))
    )
    (net (code "48") (name "Net-(R1_EP_DR-Pad1)") (class "Default")
      (node (ref "R1_EP_DR") (pin "1") (pinfunction "1_1") (pintype "bidirectional"))
      (node (ref "R_TYPE_SEL") (pin "2") (pinfunction "2_2") (pintype "bidirectional"))
      (node (ref "SJ1") (pin "2") (pinfunction "2_2") (pintype "passive"))
    )
    (net (code "49") (name "Net-(U1-ANT)") (class "Default")
      (node (ref "C3") (pin "1") (pinfunction "1_1") (pintype "passive"))
      (node (ref "L1") (pin "1") (pinfunction "1_1") (pintype "passive"))
      (node (ref "U1") (pin "P$H23") (pinfunction "ANT_P$H23") (pintype "bidirectional"))
    )
    (net (code "50") (name "Net-(U1-DCC)") (class "Default")
      (node (ref "L2") (pin "1") (pinfunction "1_1") (pintype "passive"))
      (node (ref "U1") (pin "P$B3") (pinfunction "DCC_P$B3") (pintype "output"))
    )
    (net (code "51") (name "Net-(U1-DEC1)") (class "Default")
      (node (ref "C5") (pin "1") (pinfunction "1_1") (pintype "passive"))
      (node (ref "U1") (pin "P$C1") (pinfunction "DEC1_P$C1") (pintype "power_in"))
    )
    (net (code "52") (name "Net-(U1-DEC2)") (class "Default")
      (node (ref "C13") (pin "1") (pinfunction "1_1") (pintype "passive"))
      (node (ref "U1") (pin "P$A18") (pinfunction "DEC2_P$A18") (pintype "bidirectional"))
    )
    (net (code "53") (name "Net-(U1-DEC3)") (class "Default")
      (node (ref "C11") (pin "1") (pinfunction "1_1") (pintype "passive"))
      (node (ref "U1") (pin "P$D23") (pinfunction "DEC3_P$D23") (pintype "bidirectional"))
    )
    (net (code "54") (name "Net-(U1-DEC3V3)") (class "Default")
      (node (ref "C20") (pin "1") (pinfunction "1_1") (pintype "passive"))
      (node (ref "U1") (pin "P$AC5") (pinfunction "DEC3V3_P$AC5") (pintype "bidirectional"))
    )
    (net (code "55") (name "Net-(U1-DEC5)") (class "Default")
      (node (ref "C9") (pin "1") (pinfunction "1_1") (pintype "passive"))
      (node (ref "U1") (pin "P$N24") (pinfunction "DEC5_P$N24") (pintype "bidirectional"))
    )
    (net (code "56") (name "Net-(U1-DEC6)") (class "Default")
      (node (ref "C10") (pin "1") (pinfunction "1_1") (pintype "passive"))
      (node (ref "C15") (pin "1") (pinfunction "1_1") (pintype "passive"))
      (node (ref "C16") (pin "1") (pinfunction "1_1") (pintype "passive"))
      (node (ref "L3") (pin "2") (pinfunction "2_2") (pintype "passive"))
      (node (ref "U1") (pin "P$E24") (pinfunction "DEC6_P$E24") (pintype "bidirectional"))
    )
    (net (code "57") (name "Net-(U1-P0.00{slash}XL1)") (class "Default")
      (node (ref "C17") (pin "2") (pinfunction "2_2") (pintype "passive"))
      (node (ref "U1") (pin "P$D2") (pinfunction "P0.00/XL1_P$D2") (pintype "bidirectional"))
      (node (ref "X2") (pin "1") (pinfunction "1_1") (pintype "passive"))
    )
    (net (code "58") (name "Net-(U1-P0.01{slash}XL2)") (class "Default")
      (node (ref "C18") (pin "2") (pinfunction "2_2") (pintype "passive"))
      (node (ref "U1") (pin "P$F2") (pinfunction "P0.01/XL2_P$F2") (pintype "bidirectional"))
      (node (ref "X2") (pin "2") (pinfunction "2_2") (pintype "passive"))
    )
    (net (code "59") (name "Net-(U1-XC1)") (class "Default")
      (node (ref "C1") (pin "1") (pinfunction "1_1") (pintype "passive"))
      (node (ref "U1") (pin "P$B24") (pinfunction "XC1_P$B24") (pintype "input"))
      (node (ref "X1") (pin "1") (pinfunction "1_1") (pintype "passive"))
    )
    (net (code "60") (name "Net-(U1-XC2)") (class "Default")
      (node (ref "C2") (pin "1") (pinfunction "1_1") (pintype "passive"))
      (node (ref "U1") (pin "P$A23") (pinfunction "XC2_P$A23") (pintype "output"))
      (node (ref "X1") (pin "3") (pinfunction "3_3") (pintype "passive"))
    )
    (net (code "61") (name "OUT+") (class "Default")
      (node (ref "IC2") (pin "A3") (pinfunction "OUT+_A3") (pintype "bidirectional"))
      (node (ref "TP_OP") (pin "TP") (pinfunction "TP_TP") (pintype "input"))
    )
    (net (code "62") (name "OUT-") (class "Default")
      (node (ref "IC2") (pin "C3") (pinfunction "OUT-_C3") (pintype "bidirectional"))
      (node (ref "TP_ON") (pin "TP") (pinfunction "TP_TP") (pintype "input"))
    )
    (net (code "63") (name "P0.04") (class "Default")
      (node (ref "U1") (pin "P$J1") (pinfunction "P0.04/AIN2_P$J1") (pintype "bidirectional"))
    )
    (net (code "64") (name "P0.09") (class "Default")
      (node (ref "U1") (pin "P$L24") (pinfunction "P0.09/NFC1_P$L24") (pintype "bidirectional"))
    )
    (net (code "65") (name "P0.13{slash}1.5D") (class "Default")
      (node (ref "C30") (pin "2") (pinfunction "2_2") (pintype "passive"))
      (node (ref "R5") (pin "1") (pinfunction "1_1") (pintype "bidirectional"))
      (node (ref "SW_UP") (pin "2") (pinfunction "2_2") (pintype "passive"))
    )
    (net (code "66") (name "P0.13{slash}2.6C") (class "Default")
      (node (ref "U1") (pin "P$AD8") (pinfunction "P0.13_P$AD8") (pintype "bidirectional"))
    )
    (net (code "67") (name "P0.14{slash}1.5D") (class "Default")
      (node (ref "C31") (pin "2") (pinfunction "2_2") (pintype "passive"))
      (node (ref "R8") (pin "1") (pinfunction "1_1") (pintype "bidirectional"))
      (node (ref "SW_ENT") (pin "2") (pinfunction "2_2") (pintype "passive"))
    )
    (net (code "68") (name "P0.14{slash}2.7C") (class "Default")
      (node (ref "U1") (pin "P$AC9") (pinfunction "P0.14_P$AC9") (pintype "bidirectional"))
    )
    (net (code "69") (name "P0.19") (class "Default")
      (node (ref "U1") (pin "P$AC15") (pinfunction "P0.19_P$AC15") (pintype "bidirectional"))
    )
    (net (code "70") (name "P0.20") (class "Default")
      (node (ref "U1") (pin "P$AD16") (pinfunction "P0.20_P$AD16") (pintype "bidirectional"))
    )
    (net (code "71") (name "P0.21") (class "Default")
      (node (ref "U1") (pin "P$AC17") (pinfunction "P0.21_P$AC17") (pintype "bidirectional"))
    )
    (net (code "72") (name "P0.22") (class "Default")
      (node (ref "U1") (pin "P$AD18") (pinfunction "P0.22_P$AD18") (pintype "bidirectional"))
    )
    (net (code "73") (name "P0.23") (class "Default")
      (node (ref "U1") (pin "P$AC19") (pinfunction "P0.23_P$AC19") (pintype "bidirectional"))
    )
    (net (code "74") (name "P0.24") (class "Default")
      (node (ref "U1") (pin "P$AD20") (pinfunction "P0.24_P$AD20") (pintype "bidirectional"))
    )
    (net (code "75") (name "P0.25") (class "Default")
      (node (ref "U1") (pin "P$AC21") (pinfunction "P0.25_P$AC21") (pintype "bidirectional"))
    )
    (net (code "76") (name "P0.26") (class "Default")
      (node (ref "U1") (pin "P$G1") (pinfunction "P0.26_P$G1") (pintype "bidirectional"))
    )
    (net (code "77") (name "P0.27") (class "Default")
      (node (ref "U1") (pin "P$H2") (pinfunction "P0.27_P$H2") (pintype "bidirectional"))
    )
    (net (code "78") (name "P0.28") (class "Default")
      (node (ref "U1") (pin "P$B11") (pinfunction "P0.28/AIN4_P$B11") (pintype "bidirectional"))
    )
    (net (code "79") (name "P0.29") (class "Default")
      (node (ref "U1") (pin "P$A10") (pinfunction "P0.29/AIN5_P$A10") (pintype "bidirectional"))
    )
    (net (code "80") (name "P0.30") (class "Default")
      (node (ref "U1") (pin "P$B9") (pinfunction "P0.30/AIN6_P$B9") (pintype "bidirectional"))
    )
    (net (code "81") (name "P0.31") (class "Default")
      (node (ref "U1") (pin "P$A8") (pinfunction "P0.31/AIN7_P$A8") (pintype "bidirectional"))
    )
    (net (code "82") (name "P1.01{slash}1.6C") (class "Default")
      (node (ref "Q1") (pin "1") (pinfunction "G_1") (pintype "bidirectional"))
      (node (ref "R_PWR_EPD") (pin "1") (pinfunction "1_1") (pintype "bidirectional"))
    )
    (net (code "83") (name "P1.01{slash}2.4B") (class "Default")
      (node (ref "U1") (pin "P$Y23") (pinfunction "P1.01_P$Y23") (pintype "bidirectional"))
    )
    (net (code "84") (name "P1.02{slash}1.6C") (class "Default")
      (node (ref "C29") (pin "2") (pinfunction "2_2") (pintype "passive"))
      (node (ref "R7") (pin "1") (pinfunction "1_1") (pintype "bidirectional"))
      (node (ref "SW_DN") (pin "2") (pinfunction "2_2") (pintype "passive"))
    )
    (net (code "85") (name "P1.02{slash}2.8C") (class "Default")
      (node (ref "U1") (pin "P$W24") (pinfunction "P1.02_P$W24") (pintype "bidirectional"))
    )
    (net (code "86") (name "P1.03") (class "Default")
      (node (ref "U1") (pin "P$V23") (pinfunction "P1.03_P$V23") (pintype "bidirectional"))
    )
    (net (code "87") (name "P1.04") (class "Default")
      (node (ref "U1") (pin "P$U24") (pinfunction "P1.04_P$U24") (pintype "bidirectional"))
    )
    (net (code "88") (name "P1.05") (class "Default")
      (node (ref "U1") (pin "P$T23") (pinfunction "P1.05_P$T23") (pintype "bidirectional"))
    )
    (net (code "89") (name "P1.06") (class "Default")
      (node (ref "U1") (pin "P$R24") (pinfunction "P1.06_P$R24") (pintype "bidirectional"))
    )
    (net (code "90") (name "P1.07") (class "Default")
      (node (ref "U1") (pin "P$P23") (pinfunction "P1.07_P$P23") (pintype "bidirectional"))
    )
    (net (code "91") (name "P1.09") (class "Default")
      (node (ref "U1") (pin "P$R1") (pinfunction "P1.09_P$R1") (pintype "bidirectional"))
    )
    (net (code "92") (name "P1.10") (class "Default")
      (node (ref "U1") (pin "P$A20") (pinfunction "P1.10_P$A20") (pintype "bidirectional"))
    )
    (net (code "93") (name "P1.11") (class "Default")
      (node (ref "U1") (pin "P$B19") (pinfunction "P1.11_P$B19") (pintype "bidirectional"))
    )
    (net (code "94") (name "P1.12") (class "Default")
      (node (ref "U1") (pin "P$B17") (pinfunction "P1.12_P$B17") (pintype "bidirectional"))
    )
    (net (code "95") (name "P1.13") (class "Default")
      (node (ref "U1") (pin "P$A16") (pinfunction "P1.13_P$A16") (pintype "bidirectional"))
    )
    (net (code "96") (name "P1.14") (class "Default")
      (node (ref "U1") (pin "P$B15") (pinfunction "P1.14_P$B15") (pintype "bidirectional"))
    )
    (net (code "97") (name "P1.15") (class "Default")
      (node (ref "U1") (pin "P$A14") (pinfunction "P1.15_P$A14") (pintype "bidirectional"))
    )
    (net (code "98") (name "PMIC_INT") (class "Default")
      (node (ref "IC1") (pin "A1") (pinfunction "~{INT}_A1") (pintype "bidirectional"))
      (node (ref "U1") (pin "P$T2") (pinfunction "P0.11_P$T2") (pintype "bidirectional"))
    )
    (net (code "99") (name "PREVGH") (class "Default")
      (node (ref "D5") (pin "1") (pinfunction "K_1") (pintype "bidirectional"))
      (node (ref "EPD_C9") (pin "2") (pinfunction "2_2") (pintype "passive"))
      (node (ref "J2") (pin "21") (pinfunction "21_21") (pintype "bidirectional"))
    )
    (net (code "100") (name "PREVGL") (class "Default")
      (node (ref "D2") (pin "2") (pinfunction "A_2") (pintype "bidirectional"))
      (node (ref "EPD_C11") (pin "2") (pinfunction "2_2") (pintype "passive"))
      (node (ref "J2") (pin "23") (pinfunction "23_23") (pintype "bidirectional"))
    )
    (net (code "101") (name "RESE") (class "Default")
      (node (ref "J2") (pin "3") (pinfunction "3_3") (pintype "bidirectional"))
      (node (ref "Q3") (pin "2") (pinfunction "S_2") (pintype "bidirectional"))
      (node (ref "R1_EP_DR") (pin "2") (pinfunction "2_2") (pintype "bidirectional"))
    )
    (net (code "102") (name "RESET") (class "Default")
      (node (ref "J1") (pin "6") (pinfunction "6_6") (pintype "bidirectional"))
      (node (ref "TP_RESET") (pin "TP") (pinfunction "TP_TP") (pintype "input"))
      (node (ref "U1") (pin "P$AC13") (pinfunction "P0.18/RESET_P$AC13") (pintype "bidirectional"))
    )
    (net (code "103") (name "SCK{slash}1.5B") (class "Default")
      (node (ref "J2") (pin "13") (pinfunction "13_13") (pintype "bidirectional"))
    )
    (net (code "104") (name "SCK{slash}2.2D") (class "Default")
      (node (ref "U1") (pin "P$A12") (pinfunction "P0.02/AIN0_P$A12") (pintype "bidirectional"))
    )
    (net (code "105") (name "SCL{slash}1.4C") (class "Default")
      (node (ref "IC2") (pin "C1") (pinfunction "SCL_C1") (pintype "bidirectional"))
      (node (ref "U3") (pin "7") (pinfunction "SCL_7") (pintype "input"))
    )
    (net (code "106") (name "SCL{slash}2.4C") (class "Default")
      (node (ref "IC1") (pin "B1") (pinfunction "SCL_B1") (pintype "bidirectional"))
      (node (ref "IC3") (pin "12") (pinfunction "SCX_12") (pintype "bidirectional"))
      (node (ref "R17") (pin "2") (pinfunction "2_2") (pintype "bidirectional"))
      (node (ref "R4") (pin "1") (pinfunction "1_1") (pintype "bidirectional"))
      (node (ref "TP_SCL") (pin "TP") (pinfunction "TP_TP") (pintype "input"))
      (node (ref "U1") (pin "P$M2") (pinfunction "P0.07_P$M2") (pintype "bidirectional"))
    )
    (net (code "107") (name "SDA{slash}1.4C") (class "Default")
      (node (ref "IC2") (pin "B2") (pinfunction "SDA_B2") (pintype "bidirectional"))
      (node (ref "U3") (pin "8") (pinfunction "SDA_8") (pintype "bidirectional"))
    )
    (net (code "108") (name "SDA{slash}2.4C") (class "Default")
      (node (ref "IC1") (pin "C1") (pinfunction "SDA_C1") (pintype "bidirectional"))
      (node (ref "IC3") (pin "2") (pinfunction "SDX_2") (pintype "bidirectional"))
      (node (ref "R18") (pin "2") (pinfunction "2_2") (pintype "bidirectional"))
      (node (ref "R2") (pin "1") (pinfunction "1_1") (pintype "bidirectional"))
      (node (ref "TP_SDA") (pin "TP") (pinfunction "TP_TP") (pintype "input"))
      (node (ref "U1") (pin "P$L1") (pinfunction "P0.06_P$L1") (pintype "bidirectional"))
    )
    (net (code "109") (name "SWDCLK") (class "Default")
      (node (ref "J1") (pin "4") (pinfunction "4_4") (pintype "bidirectional"))
      (node (ref "TP_SWDCLK") (pin "TP") (pinfunction "TP_TP") (pintype "input"))
      (node (ref "U1") (pin "P$AA24") (pinfunction "SWDCLK_P$AA24") (pintype "input"))
    )
    (net (code "110") (name "SWDIO") (class "Default")
      (node (ref "J1") (pin "2") (pinfunction "2_2") (pintype "bidirectional"))
      (node (ref "TP_SWDIO") (pin "TP") (pinfunction "TP_TP") (pintype "input"))
      (node (ref "U1") (pin "P$AC24") (pinfunction "SWDIO_P$AC24") (pintype "bidirectional"))
    )
    (net (code "111") (name "SWO") (class "Default")
      (node (ref "TP_SWO") (pin "TP") (pinfunction "TP_TP") (pintype "input"))
      (node (ref "U1") (pin "P$AD22") (pinfunction "P1.00_P$AD22") (pintype "bidirectional"))
    )
    (net (code "112") (name "VBAT{slash}1.2A") (class "Default")
      (node (ref "C27") (pin "2") (pinfunction "2_2") (pintype "passive"))
      (node (ref "TP_VBAT") (pin "TP") (pinfunction "TP_TP") (pintype "input"))
      (node (ref "U3") (pin "2") (pinfunction "CELL_2") (pintype "power_in"))
      (node (ref "U3") (pin "3") (pinfunction "VDD_3") (pintype "power_in"))
    )
    (net (code "113") (name "VBAT{slash}2.5C") (class "Default")
      (node (ref "C37") (pin "2") (pinfunction "2_2") (pintype "passive"))
      (node (ref "IC1") (pin "C2") (pinfunction "BAT_C2") (pintype "bidirectional"))
    )
    (net (code "114") (name "VBUS{slash}1.5D") (class "Default")
      (node (ref "C42") (pin "1") (pinfunction "1_1") (pintype "passive"))
      (node (ref "C43") (pin "1") (pinfunction "1_1") (pintype "passive"))
      (node (ref "D3") (pin "5") (pinfunction "VBUS_5") (pintype "bidirectional"))
      (node (ref "J4") (pin "A4_B9") (pinfunction "VBUS_A4_B9") (pintype "power_in"))
      (node (ref "J4") (pin "A9_B4") (pinfunction "VBUS_A9_B4") (pintype "power_in"))
    )
    (net (code "115") (name "VBUS{slash}2.6D") (class "Default")
      (node (ref "C21") (pin "1") (pinfunction "1_1") (pintype "passive"))
      (node (ref "C38") (pin "2") (pinfunction "2_2") (pintype "passive"))
      (node (ref "IC1") (pin "A2") (pinfunction "IN_A2") (pintype "bidirectional"))
      (node (ref "U1") (pin "P$AD2") (pinfunction "VBUS_P$AD2") (pintype "power_in"))
    )
    (net (code "116") (name "VREG") (class "Default")
      (node (ref "C23") (pin "2") (pinfunction "2_2") (pintype "passive"))
      (node (ref "C24") (pin "2") (pinfunction "2_2") (pintype "passive"))
      (node (ref "C39") (pin "1") (pinfunction "1_1") (pintype "passive"))
      (node (ref "IC1") (pin "B2") (pinfunction "SYS_B2") (pintype "bidirectional"))
      (node (ref "IC9") (pin "A1") (pinfunction "EN_A1") (pintype "bidirectional"))
      (node (ref "IC9") (pin "A2") (pinfunction "VIN_1_A2") (pintype "bidirectional"))
      (node (ref "IC9") (pin "A3") (pinfunction "VIN_2_A3") (pintype "bidirectional"))
      (node (ref "TP_VREG") (pin "TP") (pinfunction "TP_TP") (pintype "input"))
    )
    (net (code "117") (name "unconnected-(ANT1-NC-Pad2)") (class "Default")
      (node (ref "ANT1") (pin "2") (pinfunction "NC_2") (pintype "no_connect"))
    )
    (net (code "118") (name "unconnected-(IC3-ASCL-Pad11)") (class "Default")
      (node (ref "IC3") (pin "11") (pinfunction "ASCL_11") (pintype "bidirectional"))
    )
    (net (code "119") (name "unconnected-(IC3-ASDA-Pad4)") (class "Default")
      (node (ref "IC3") (pin "4") (pinfunction "ASDA_4") (pintype "bidirectional"))
    )
    (net (code "120") (name "unconnected-(J2-Pad1)") (class "Default")
      (node (ref "J2") (pin "1") (pinfunction "1_1") (pintype "bidirectional"))
    )
    (net (code "121") (name "unconnected-(J2-Pad6)") (class "Default")
      (node (ref "J2") (pin "6") (pinfunction "6_6") (pintype "bidirectional"))
    )
    (net (code "122") (name "unconnected-(J2-Pad7)") (class "Default")
      (node (ref "J2") (pin "7") (pinfunction "7_7") (pintype "bidirectional"))
    )
    (net (code "123") (name "unconnected-(J4-SBU1-PadA8)") (class "Default")
      (node (ref "J4") (pin "A8") (pinfunction "SBU1_A8") (pintype "bidirectional"))
    )
    (net (code "124") (name "unconnected-(J4-SBU2-PadB8)") (class "Default")
      (node (ref "J4") (pin "B8") (pinfunction "SBU2_B8") (pintype "bidirectional"))
    )
    (net (code "125") (name "unconnected-(U1-DCCH-PadP$AB2)") (class "Default")
      (node (ref "U1") (pin "P$AB2") (pinfunction "DCCH_P$AB2") (pintype "bidirectional"))
    )
    (net (code "126") (name "unconnected-(U1-DEC4-PadP$B5)") (class "Default")
      (node (ref "U1") (pin "P$B5") (pinfunction "DEC4_P$B5") (pintype "power_in"))
    )
  )
)
